# SD_card.net
KiCad netlist of a schematic drawn in Altium Designer
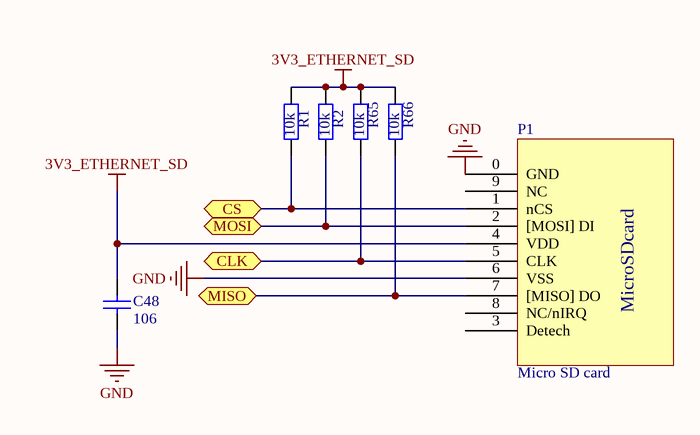
[diagram p0: SD_card.SchDoc]

(export (version "E")
  (design (tool "Eeschema 10.0.6"))
  (components
    (comp (ref "C48") (value "106") (footprint "0603_Cap") (libsource (lib "CMN") (part "Ceramic Capacitor")))
    (comp (ref "P1")
      (value "Micro SD card")
      (footprint "MicroSD")
      (libsource (lib "Component") (part "Micro SD card"))
    )
    (comp (ref "R1") (value "10k") (footprint "0603_Res") (libsource (lib "CMN") (part "Resistor")))
    (comp (ref "R2") (value "10k") (footprint "0603_Res") (libsource (lib "CMN") (part "Resistor")))
    (comp (ref "R65") (value "10k") (footprint "0603_Res") (libsource (lib "CMN") (part "Resistor")))
    (comp (ref "R66") (value "10k") (footprint "0603_Res") (libsource (lib "CMN") (part "Resistor")))
  )
  (nets
    (net (code "1") (name "/CLK") (class "Default")
      (node (ref "P1") (pin "5") (pinfunction "CLK_5") (pintype "passive"))
      (node (ref "R65") (pin "1") (pinfunction "1_1") (pintype "passive"))
    )
    (net (code "2") (name "/CS") (class "Default")
      (node (ref "P1") (pin "1") (pinfunction "nCS_1") (pintype "passive"))
      (node (ref "R1") (pin "1") (pinfunction "1_1") (pintype "passive"))
    )
    (net (code "3") (name "/MISO") (class "Default")
      (node (ref "P1") (pin "7") (pinfunction "[MISO]_DO_7") (pintype "passive"))
      (node (ref "R66") (pin "1") (pinfunction "1_1") (pintype "passive"))
    )
    (net (code "4") (name "/MOSI") (class "Default")
      (node (ref "P1") (pin "2") (pinfunction "[MOSI]_DI_2") (pintype "passive"))
      (node (ref "R2") (pin "1") (pinfunction "1_1") (pintype "passive"))
    )
    (net (code "5") (name "3V3_ETHERNET_SD") (class "Default")
      (node (ref "C48") (pin "1") (pinfunction "1_1") (pintype "passive"))
      (node (ref "P1") (pin "4") (pinfunction "VDD_4") (pintype "passive"))
      (node (ref "R1") (pin "2") (pinfunction "2_2") (pintype "passive"))
      (node (ref "R2") (pin "2") (pinfunction "2_2") (pintype "passive"))
      (node (ref "R65") (pin "2") (pinfunction "2_2") (pintype "passive"))
      (node (ref "R66") (pin "2") (pinfunction "2_2") (pintype "passive"))
    )
    (net (code "6") (name "GND") (class "Default")
      (node (ref "C48") (pin "2") (pinfunction "2_2") (pintype "passive"))
      (node (ref "P1") (pin "0") (pinfunction "GND_0") (pintype "passive"))
      (node (ref "P1") (pin "6") (pinfunction "VSS_6") (pintype "passive"))
    )
    (net (code "7") (name "unconnected-(P1-Detech-Pad3)") (class "Default")
      (node (ref "P1") (pin "3") (pinfunction "Detech_3") (pintype "passive"))
    )
    (net (code "8") (name "unconnected-(P1-NC-Pad9)") (class "Default")
      (node (ref "P1") (pin "9") (pinfunction "NC_9") (pintype "passive"))
    )
    (net (code "9") (name "unconnected-(P1-NC{slash}nIRQ-Pad8)") (class "Default")
      (node (ref "P1") (pin "8") (pinfunction "NC/nIRQ_8") (pintype "passive"))
    )
  )
)
